# labortagebadge_2011.net
KiCad netlist of a schematic drawn in EAGLE
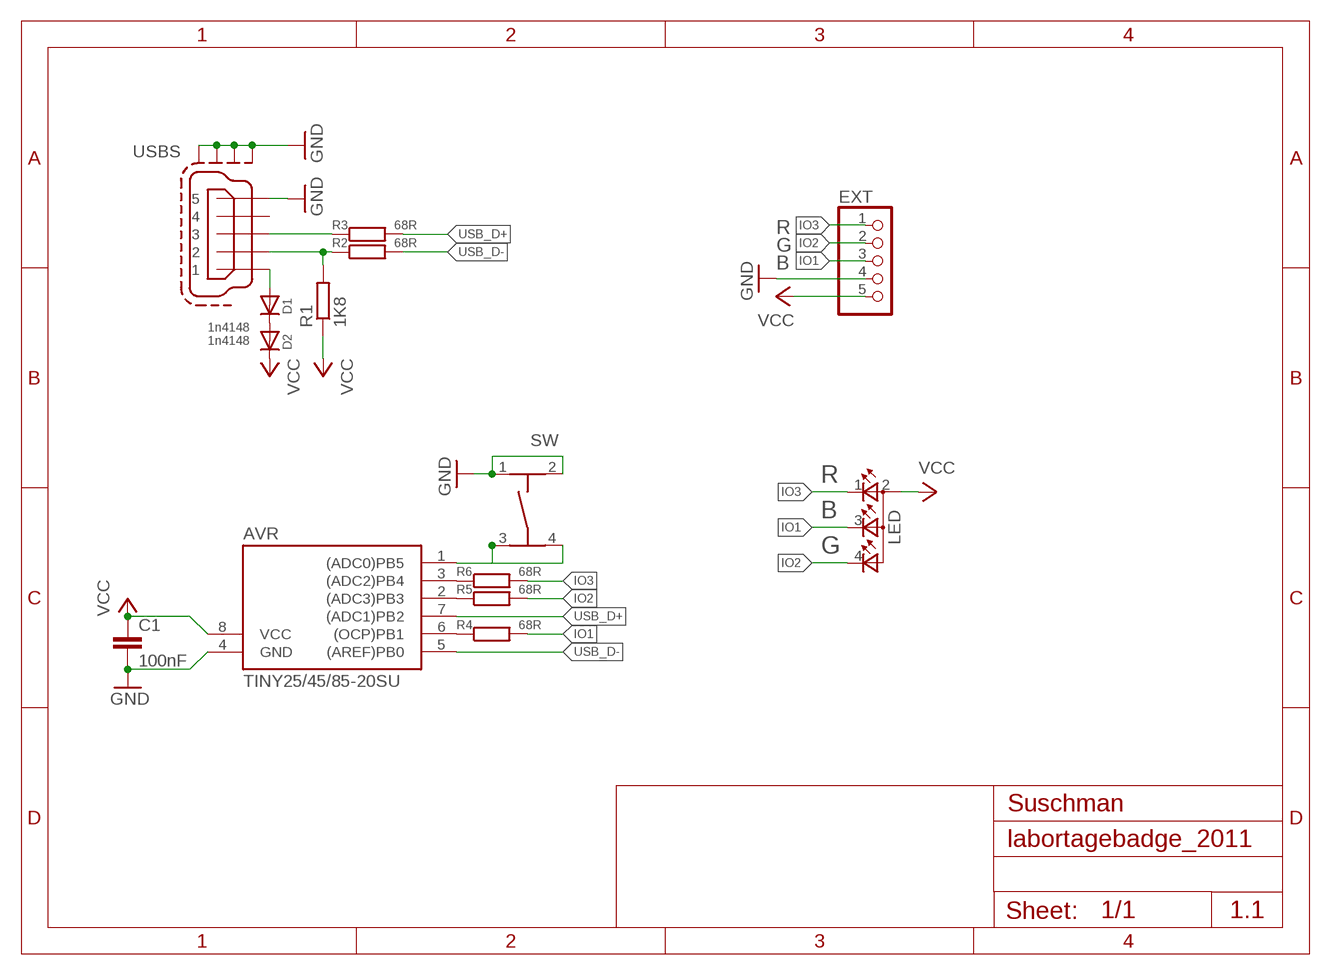
[diagram p0: schematic, sheet 1]

(export (version "E")
  (design (tool "Eeschema 10.0.6"))
  (components
    (comp (ref "AVR")
      (value "TINY25/45/85-20SU")
      (footprint "eagle-import:SOIC8")
      (libsource (lib "eagle-import") (part "TINY25/45/85-20SU"))
    )
    (comp (ref "C1")
      (value "100nF")
      (footprint "eagle-import:C0805K")
      (libsource (lib "eagle-import") (part "C-EUC0805K"))
    )
    (comp (ref "D1")
      (value "1n4148")
      (footprint "eagle-import:MINIMELF")
      (libsource (lib "eagle-import") (part "DIODE-MINIMELF"))
    )
    (comp (ref "D2")
      (value "1n4148")
      (footprint "eagle-import:MINIMELF")
      (libsource (lib "eagle-import") (part "DIODE-MINIMELF"))
    )
    (comp (ref "EXT")
      (value "PINHD-1X5")
      (footprint "eagle-import:1X05")
      (libsource (lib "eagle-import") (part "PINHD-1X5"))
    )
    (comp (ref "LED")
      (value "TOPLED-3")
      (footprint "eagle-import:P-LCC-4-3")
      (libsource (lib "eagle-import") (part "TOPLED-3"))
    )
    (comp (ref "R1")
      (value "1K8")
      (footprint "eagle-import:R0805")
      (libsource (lib "eagle-import") (part "R-EU_R0805"))
    )
    (comp (ref "R2")
      (value "68R")
      (footprint "eagle-import:R0805")
      (libsource (lib "eagle-import") (part "R-EU_R0805"))
    )
    (comp (ref "R3")
      (value "68R")
      (footprint "eagle-import:R0805")
      (libsource (lib "eagle-import") (part "R-EU_R0805"))
    )
    (comp (ref "R4")
      (value "68R")
      (footprint "eagle-import:R0805")
      (libsource (lib "eagle-import") (part "R-EU_R0805"))
    )
    (comp (ref "R5")
      (value "68R")
      (footprint "eagle-import:R0805")
      (libsource (lib "eagle-import") (part "R-EU_R0805"))
    )
    (comp (ref "R6")
      (value "68R")
      (footprint "eagle-import:R0805")
      (libsource (lib "eagle-import") (part "R-EU_R0805"))
    )
    (comp (ref "SW")
      (value "TASTER-9314_SMD")
      (footprint "eagle-import:TASTER-9314_SMD")
      (libsource (lib "eagle-import") (part "TASTER-9314_SMD"))
    )
    (comp (ref "USB")
      (value "MINI-USB-SCHIELD-32005-201")
      (footprint "eagle-import:32005-201")
      (libsource (lib "eagle-import") (part "MINI-USB-SCHIELD-32005-201"))
    )
  )
  (nets
    (net (code "1") (name "GND") (class "Default")
      (node (ref "AVR") (pin "4") (pinfunction "GND_4") (pintype "power_in"))
      (node (ref "C1") (pin "2") (pinfunction "2_2") (pintype "passive"))
      (node (ref "EXT") (pin "4") (pinfunction "4_4") (pintype "passive"))
      (node (ref "SW") (pin "1") (pinfunction "1_1") (pintype "passive"))
      (node (ref "SW") (pin "2") (pinfunction "2_2") (pintype "passive"))
      (node (ref "USB") (pin "5") (pinfunction "5_5") (pintype "passive"))
      (node (ref "USB") (pin "M1") (pinfunction "S1_M1") (pintype "passive"))
      (node (ref "USB") (pin "M2") (pinfunction "S2_M2") (pintype "passive"))
      (node (ref "USB") (pin "M3") (pinfunction "S3_M3") (pintype "passive"))
      (node (ref "USB") (pin "M4") (pinfunction "S4_M4") (pintype "passive"))
    )
    (net (code "2") (name "IO1") (class "Default")
      (node (ref "EXT") (pin "3") (pinfunction "3_3") (pintype "passive"))
      (node (ref "LED") (pin "3") (pinfunction "CBLUE_3") (pintype "passive"))
      (node (ref "R4") (pin "2") (pinfunction "2_2") (pintype "passive"))
    )
    (net (code "3") (name "IO2") (class "Default")
      (node (ref "EXT") (pin "2") (pinfunction "2_2") (pintype "passive"))
      (node (ref "LED") (pin "4") (pinfunction "CGREEN_4") (pintype "passive"))
      (node (ref "R5") (pin "2") (pinfunction "2_2") (pintype "passive"))
    )
    (net (code "4") (name "IO3") (class "Default")
      (node (ref "EXT") (pin "1") (pinfunction "1_1") (pintype "passive"))
      (node (ref "LED") (pin "1") (pinfunction "CRED_1") (pintype "passive"))
      (node (ref "R6") (pin "2") (pinfunction "2_2") (pintype "passive"))
    )
    (net (code "5") (name "Net-(AVR-(ADC0)PB5)") (class "Default")
      (node (ref "AVR") (pin "1") (pinfunction "(ADC0)PB5_1") (pintype "bidirectional"))
      (node (ref "SW") (pin "3") (pinfunction "3_3") (pintype "passive"))
      (node (ref "SW") (pin "4") (pinfunction "4_4") (pintype "passive"))
    )
    (net (code "6") (name "Net-(AVR-(ADC2)PB4)") (class "Default")
      (node (ref "AVR") (pin "3") (pinfunction "(ADC2)PB4_3") (pintype "bidirectional"))
      (node (ref "R6") (pin "1") (pinfunction "1_1") (pintype "passive"))
    )
    (net (code "7") (name "Net-(AVR-(ADC3)PB3)") (class "Default")
      (node (ref "AVR") (pin "2") (pinfunction "(ADC3)PB3_2") (pintype "bidirectional"))
      (node (ref "R5") (pin "1") (pinfunction "1_1") (pintype "passive"))
    )
    (net (code "8") (name "Net-(AVR-(OCP)PB1)") (class "Default")
      (node (ref "AVR") (pin "6") (pinfunction "(OCP)PB1_6") (pintype "bidirectional"))
      (node (ref "R4") (pin "1") (pinfunction "1_1") (pintype "passive"))
    )
    (net (code "9") (name "Net-(D1-PadA)") (class "Default")
      (node (ref "D1") (pin "A") (pinfunction "A_A") (pintype "passive"))
      (node (ref "USB") (pin "1") (pinfunction "1_1") (pintype "passive"))
    )
    (net (code "10") (name "Net-(D1-PadC)") (class "Default")
      (node (ref "D1") (pin "C") (pinfunction "C_C") (pintype "passive"))
      (node (ref "D2") (pin "A") (pinfunction "A_A") (pintype "passive"))
    )
    (net (code "11") (name "Net-(R1-Pad2)") (class "Default")
      (node (ref "R1") (pin "2") (pinfunction "2_2") (pintype "passive"))
      (node (ref "R2") (pin "1") (pinfunction "1_1") (pintype "passive"))
      (node (ref "USB") (pin "2") (pinfunction "2_2") (pintype "passive"))
    )
    (net (code "12") (name "Net-(R3-Pad1)") (class "Default")
      (node (ref "R3") (pin "1") (pinfunction "1_1") (pintype "passive"))
      (node (ref "USB") (pin "3") (pinfunction "3_3") (pintype "passive"))
    )
    (net (code "13") (name "USB_D+") (class "Default")
      (node (ref "AVR") (pin "7") (pinfunction "(ADC1)PB2_7") (pintype "bidirectional"))
      (node (ref "R3") (pin "2") (pinfunction "2_2") (pintype "passive"))
    )
    (net (code "14") (name "USB_D-") (class "Default")
      (node (ref "AVR") (pin "5") (pinfunction "(AREF)PB0_5") (pintype "bidirectional"))
      (node (ref "R2") (pin "2") (pinfunction "2_2") (pintype "passive"))
    )
    (net (code "15") (name "VCC") (class "Default")
      (node (ref "AVR") (pin "8") (pinfunction "VCC_8") (pintype "power_in"))
      (node (ref "C1") (pin "1") (pinfunction "1_1") (pintype "passive"))
      (node (ref "D2") (pin "C") (pinfunction "C_C") (pintype "passive"))
      (node (ref "EXT") (pin "5") (pinfunction "5_5") (pintype "passive"))
      (node (ref "LED") (pin "2") (pinfunction "A2_2") (pintype "passive"))
      (node (ref "R1") (pin "1") (pinfunction "1_1") (pintype "passive"))
    )
    (net (code "16") (name "unconnected-(USB-Pad4)") (class "Default")
      (node (ref "USB") (pin "4") (pinfunction "4_4") (pintype "passive"))
    )
  )
)
